# Sheet1.net
KiCad netlist of a schematic drawn in Altium Designer
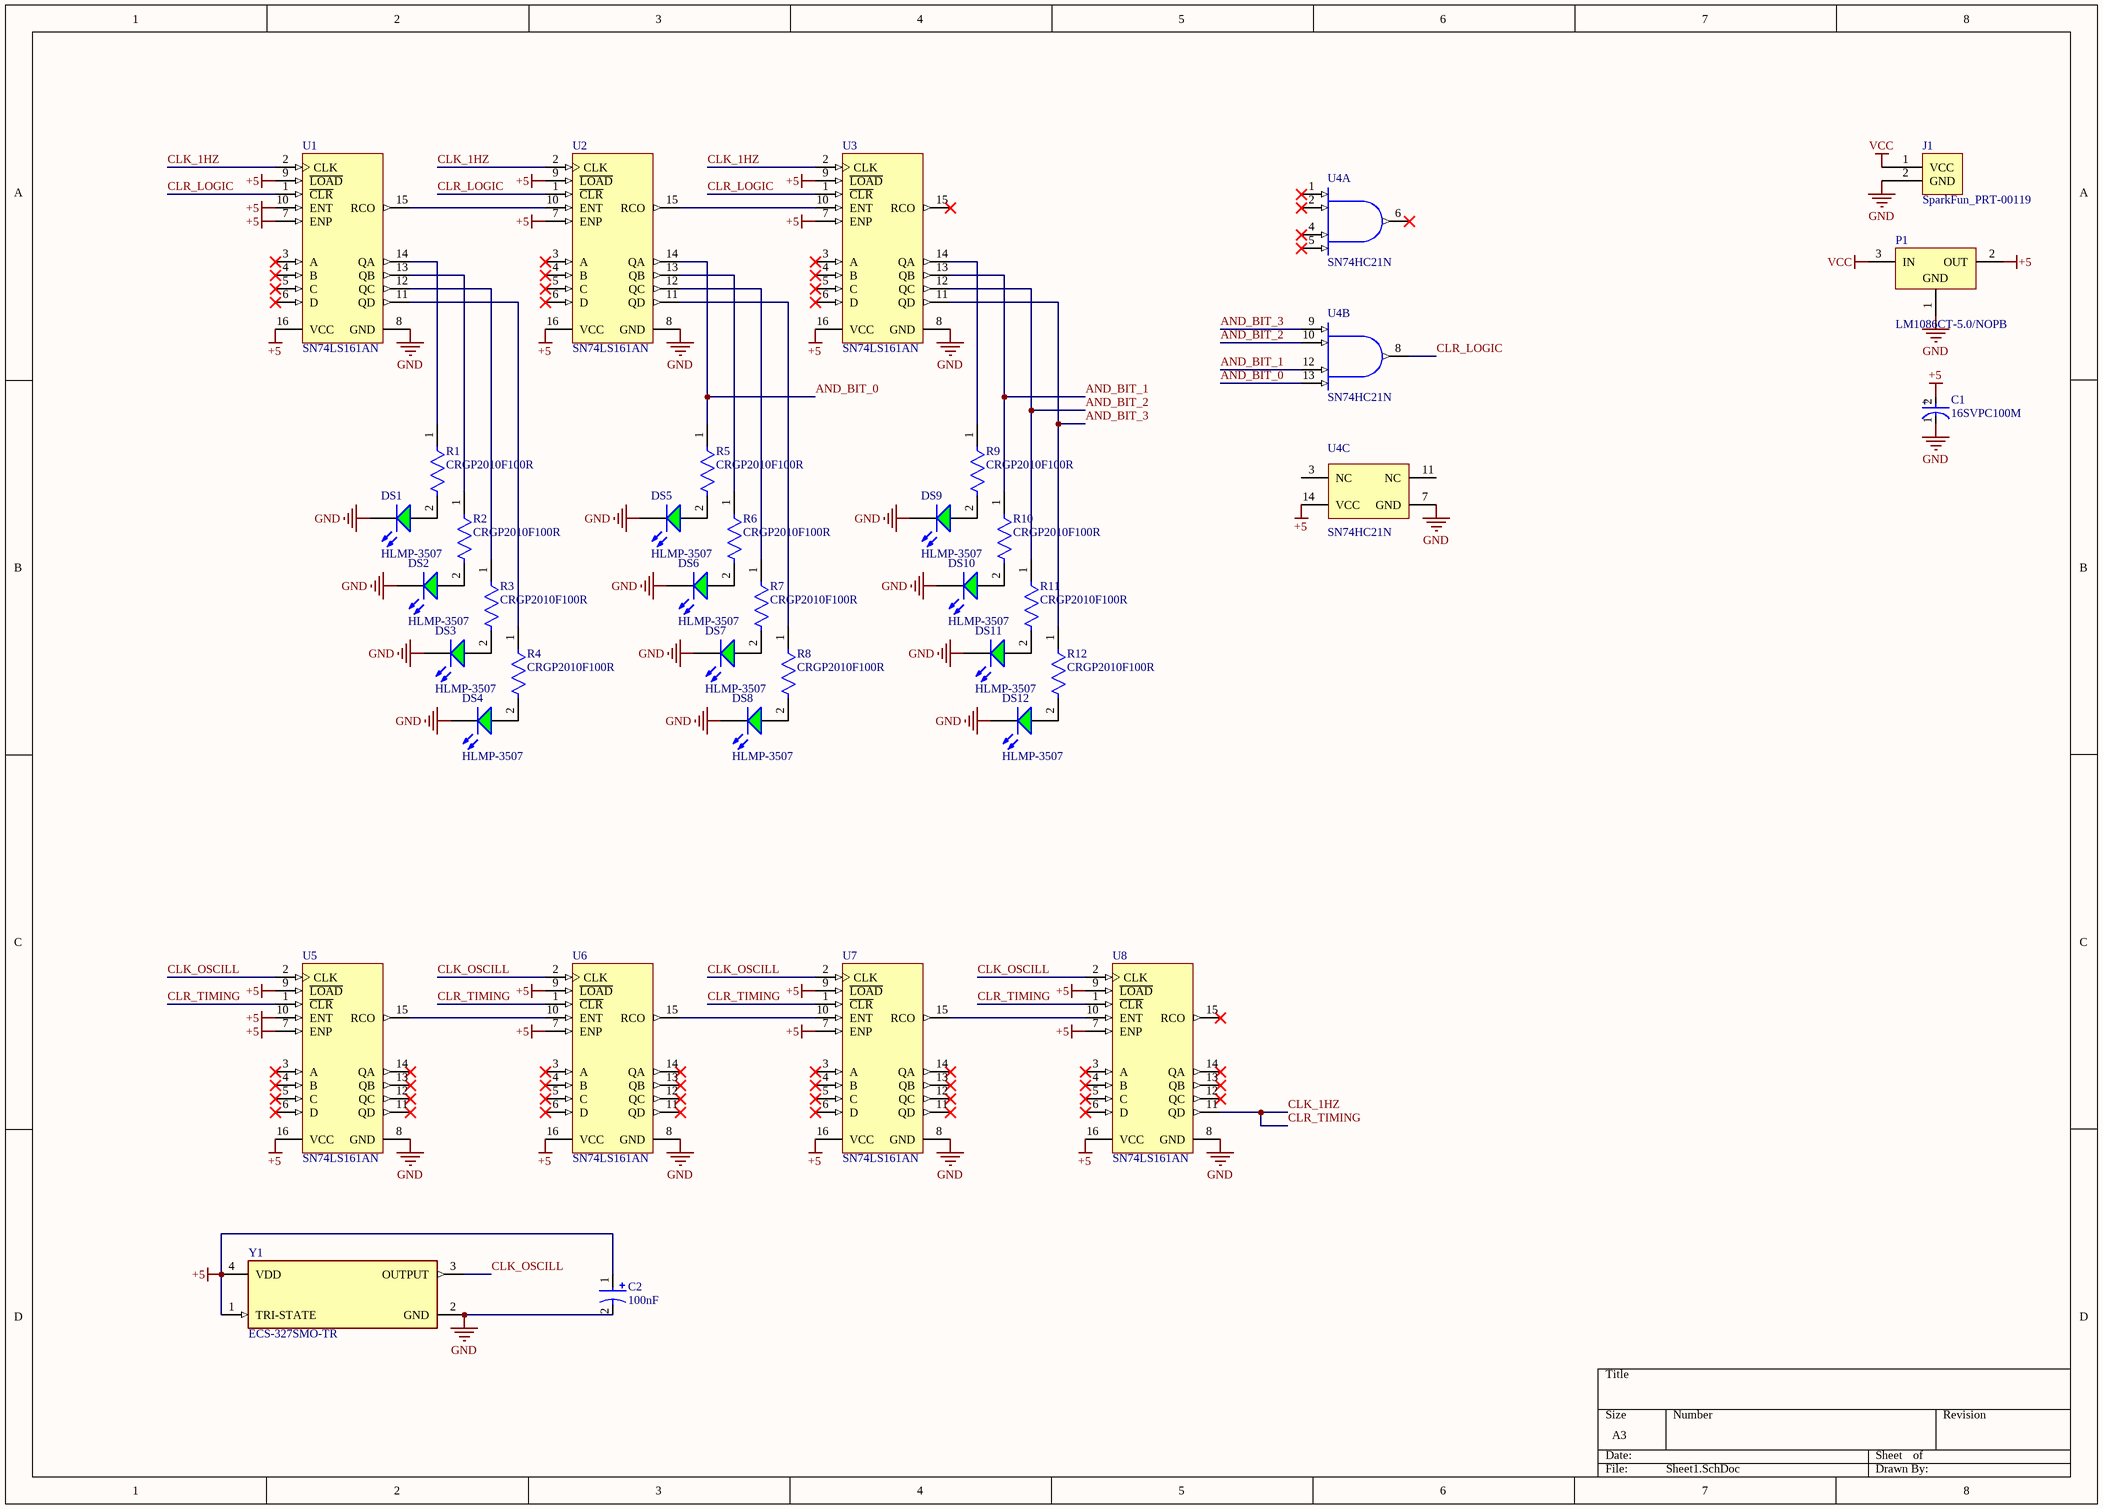
[diagram p0: Sheet1.SchDoc]

(export (version "E")
  (design (tool "Eeschema 10.0.6"))
  (components
    (comp (ref "C1")
      (value "16SVPC100M")
      (footprint "FP-OS-CON-SMT-C6-MFG")
      (description "Conductive Polymer Aluminum Solid Capacitors (OS-CON) 100uF ±20% 16V")
      (fields (field (name "VOLTAGE") "16V") (field (name "TOLERANCE") "20%"))
      (libsource (lib "Altium Content Vault") (part "a00bbbee19879c290e62620ae7e47b1"))
    )
    (comp (ref "C2")
      (value "100nF")
      (footprint "WurthElektronik_885012208030-Footprint-1")
      (description "Cap, 0.1ΜF, 16V, 10%, X7R, 1206")
      (fields (field (name "Comment") "WurthElektronik_885012208030"))
      (libsource (lib "Manus VR") (part "Capacitor_Polarized"))
    )
    (comp (ref "DS1")
      (value "HLMP-3507")
      (footprint "AVAG-HLMP-3507")
      (description "T-1 3/4 (5 mm) Diffused LED Lamp, Green, 2.1 V, -20 to 100 degC, 2-Pin THD, RoHS, Bulk")
      (fields (field (name "MANUFACTURER") "Avago"))
      (libsource (lib "Altium Content Vault") (part "LED-GREEN-AK-2"))
    )
    (comp (ref "DS2")
      (value "HLMP-3507")
      (footprint "AVAG-HLMP-3507")
      (description "T-1 3/4 (5 mm) Diffused LED Lamp, Green, 2.1 V, -20 to 100 degC, 2-Pin THD, RoHS, Bulk")
      (fields (field (name "MANUFACTURER") "Avago"))
      (libsource (lib "Altium Content Vault") (part "LED-GREEN-AK-2"))
    )
    (comp (ref "DS3")
      (value "HLMP-3507")
      (footprint "AVAG-HLMP-3507")
      (description "T-1 3/4 (5 mm) Diffused LED Lamp, Green, 2.1 V, -20 to 100 degC, 2-Pin THD, RoHS, Bulk")
      (fields (field (name "MANUFACTURER") "Avago"))
      (libsource (lib "Altium Content Vault") (part "LED-GREEN-AK-2"))
    )
    (comp (ref "DS4")
      (value "HLMP-3507")
      (footprint "AVAG-HLMP-3507")
      (description "T-1 3/4 (5 mm) Diffused LED Lamp, Green, 2.1 V, -20 to 100 degC, 2-Pin THD, RoHS, Bulk")
      (fields (field (name "MANUFACTURER") "Avago"))
      (libsource (lib "Altium Content Vault") (part "LED-GREEN-AK-2"))
    )
    (comp (ref "DS5")
      (value "HLMP-3507")
      (footprint "AVAG-HLMP-3507")
      (description "T-1 3/4 (5 mm) Diffused LED Lamp, Green, 2.1 V, -20 to 100 degC, 2-Pin THD, RoHS, Bulk")
      (fields (field (name "MANUFACTURER") "Avago"))
      (libsource (lib "Altium Content Vault") (part "LED-GREEN-AK-2"))
    )
    (comp (ref "DS6")
      (value "HLMP-3507")
      (footprint "AVAG-HLMP-3507")
      (description "T-1 3/4 (5 mm) Diffused LED Lamp, Green, 2.1 V, -20 to 100 degC, 2-Pin THD, RoHS, Bulk")
      (fields (field (name "MANUFACTURER") "Avago"))
      (libsource (lib "Altium Content Vault") (part "LED-GREEN-AK-2"))
    )
    (comp (ref "DS7")
      (value "HLMP-3507")
      (footprint "AVAG-HLMP-3507")
      (description "T-1 3/4 (5 mm) Diffused LED Lamp, Green, 2.1 V, -20 to 100 degC, 2-Pin THD, RoHS, Bulk")
      (fields (field (name "MANUFACTURER") "Avago"))
      (libsource (lib "Altium Content Vault") (part "LED-GREEN-AK-2"))
    )
    (comp (ref "DS8")
      (value "HLMP-3507")
      (footprint "AVAG-HLMP-3507")
      (description "T-1 3/4 (5 mm) Diffused LED Lamp, Green, 2.1 V, -20 to 100 degC, 2-Pin THD, RoHS, Bulk")
      (fields (field (name "MANUFACTURER") "Avago"))
      (libsource (lib "Altium Content Vault") (part "LED-GREEN-AK-2"))
    )
    (comp (ref "DS9")
      (value "HLMP-3507")
      (footprint "AVAG-HLMP-3507")
      (description "T-1 3/4 (5 mm) Diffused LED Lamp, Green, 2.1 V, -20 to 100 degC, 2-Pin THD, RoHS, Bulk")
      (fields (field (name "MANUFACTURER") "Avago"))
      (libsource (lib "Altium Content Vault") (part "LED-GREEN-AK-2"))
    )
    (comp (ref "DS10")
      (value "HLMP-3507")
      (footprint "AVAG-HLMP-3507")
      (description "T-1 3/4 (5 mm) Diffused LED Lamp, Green, 2.1 V, -20 to 100 degC, 2-Pin THD, RoHS, Bulk")
      (fields (field (name "MANUFACTURER") "Avago"))
      (libsource (lib "Altium Content Vault") (part "LED-GREEN-AK-2"))
    )
    (comp (ref "DS11")
      (value "HLMP-3507")
      (footprint "AVAG-HLMP-3507")
      (description "T-1 3/4 (5 mm) Diffused LED Lamp, Green, 2.1 V, -20 to 100 degC, 2-Pin THD, RoHS, Bulk")
      (fields (field (name "MANUFACTURER") "Avago"))
      (libsource (lib "Altium Content Vault") (part "LED-GREEN-AK-2"))
    )
    (comp (ref "DS12")
      (value "HLMP-3507")
      (footprint "AVAG-HLMP-3507")
      (description "T-1 3/4 (5 mm) Diffused LED Lamp, Green, 2.1 V, -20 to 100 degC, 2-Pin THD, RoHS, Bulk")
      (fields (field (name "MANUFACTURER") "Avago"))
      (libsource (lib "Altium Content Vault") (part "LED-GREEN-AK-2"))
    )
    (comp (ref "J1")
      (value "SparkFun_PRT-00119")
      (footprint "SparkFun_PRT-00119-Footprint-1")
      (description "Simple 6.5mm barrel jack connector")
      (fields (field (name "MANUFACTURER") "SparkFun") (field (name "MPN") "PRT-00119"))
      (libsource (lib "Manus VR") (part "SparkFun_PRT-00119-Symbol-1"))
    )
    (comp (ref "P1")
      (value "LM1086CT-5.0/NOPB")
      (footprint "NDE0003A")
      (description "1.5A Low Dropout Positive Regulators, 3-pin TO-220, Pb-Free")
      (fields (field (name "MANUFACTURER") "Texas Instruments"))
      (libsource (lib "Altium Content Vault") (part "PM-REG-LM1086-SIL3"))
    )
    (comp (ref "R1")
      (value "CRGP2010F100R")
      (footprint "FP-CRGP2010-IPC_C")
      (description "CRGP2010 100Ω 1.25W ±100ppm/°C 1% 400V")
      (fields
        (field (name "MANUFACTURER") "TE")
        (field (name "OCTOPART") "https://octopart.com/crgp2010f100r-te+connectivity-91018964")
      )
      (libsource (lib "Altium Content Vault") (part "1029c3af85768c4190bb7ad29bc67b5"))
    )
    (comp (ref "R2")
      (value "CRGP2010F100R")
      (footprint "FP-CRGP2010-IPC_C")
      (description "CRGP2010 100Ω 1.25W ±100ppm/°C 1% 400V")
      (fields
        (field (name "MANUFACTURER") "TE")
        (field (name "OCTOPART") "https://octopart.com/crgp2010f100r-te+connectivity-91018964")
      )
      (libsource (lib "Altium Content Vault") (part "1029c3af85768c4190bb7ad29bc67b5"))
    )
    (comp (ref "R3")
      (value "CRGP2010F100R")
      (footprint "FP-CRGP2010-IPC_C")
      (description "CRGP2010 100Ω 1.25W ±100ppm/°C 1% 400V")
      (fields
        (field (name "MANUFACTURER") "TE")
        (field (name "OCTOPART") "https://octopart.com/crgp2010f100r-te+connectivity-91018964")
      )
      (libsource (lib "Altium Content Vault") (part "1029c3af85768c4190bb7ad29bc67b5"))
    )
    (comp (ref "R4")
      (value "CRGP2010F100R")
      (footprint "FP-CRGP2010-IPC_C")
      (description "CRGP2010 100Ω 1.25W ±100ppm/°C 1% 400V")
      (fields
        (field (name "MANUFACTURER") "TE")
        (field (name "OCTOPART") "https://octopart.com/crgp2010f100r-te+connectivity-91018964")
      )
      (libsource (lib "Altium Content Vault") (part "1029c3af85768c4190bb7ad29bc67b5"))
    )
    (comp (ref "R5")
      (value "CRGP2010F100R")
      (footprint "FP-CRGP2010-IPC_C")
      (description "CRGP2010 100Ω 1.25W ±100ppm/°C 1% 400V")
      (fields
        (field (name "MANUFACTURER") "TE")
        (field (name "OCTOPART") "https://octopart.com/crgp2010f100r-te+connectivity-91018964")
      )
      (libsource (lib "Altium Content Vault") (part "1029c3af85768c4190bb7ad29bc67b5"))
    )
    (comp (ref "R6")
      (value "CRGP2010F100R")
      (footprint "FP-CRGP2010-IPC_C")
      (description "CRGP2010 100Ω 1.25W ±100ppm/°C 1% 400V")
      (fields
        (field (name "MANUFACTURER") "TE")
        (field (name "OCTOPART") "https://octopart.com/crgp2010f100r-te+connectivity-91018964")
      )
      (libsource (lib "Altium Content Vault") (part "1029c3af85768c4190bb7ad29bc67b5"))
    )
    (comp (ref "R7")
      (value "CRGP2010F100R")
      (footprint "FP-CRGP2010-IPC_C")
      (description "CRGP2010 100Ω 1.25W ±100ppm/°C 1% 400V")
      (fields
        (field (name "MANUFACTURER") "TE")
        (field (name "OCTOPART") "https://octopart.com/crgp2010f100r-te+connectivity-91018964")
      )
      (libsource (lib "Altium Content Vault") (part "1029c3af85768c4190bb7ad29bc67b5"))
    )
    (comp (ref "R8")
      (value "CRGP2010F100R")
      (footprint "FP-CRGP2010-IPC_C")
      (description "CRGP2010 100Ω 1.25W ±100ppm/°C 1% 400V")
      (fields
        (field (name "MANUFACTURER") "TE")
        (field (name "OCTOPART") "https://octopart.com/crgp2010f100r-te+connectivity-91018964")
      )
      (libsource (lib "Altium Content Vault") (part "1029c3af85768c4190bb7ad29bc67b5"))
    )
    (comp (ref "R9")
      (value "CRGP2010F100R")
      (footprint "FP-CRGP2010-IPC_C")
      (description "CRGP2010 100Ω 1.25W ±100ppm/°C 1% 400V")
      (fields
        (field (name "MANUFACTURER") "TE")
        (field (name "OCTOPART") "https://octopart.com/crgp2010f100r-te+connectivity-91018964")
      )
      (libsource (lib "Altium Content Vault") (part "1029c3af85768c4190bb7ad29bc67b5"))
    )
    (comp (ref "R10")
      (value "CRGP2010F100R")
      (footprint "FP-CRGP2010-IPC_C")
      (description "CRGP2010 100Ω 1.25W ±100ppm/°C 1% 400V")
      (fields
        (field (name "MANUFACTURER") "TE")
        (field (name "OCTOPART") "https://octopart.com/crgp2010f100r-te+connectivity-91018964")
      )
      (libsource (lib "Altium Content Vault") (part "1029c3af85768c4190bb7ad29bc67b5"))
    )
    (comp (ref "R11")
      (value "CRGP2010F100R")
      (footprint "FP-CRGP2010-IPC_C")
      (description "CRGP2010 100Ω 1.25W ±100ppm/°C 1% 400V")
      (fields
        (field (name "MANUFACTURER") "TE")
        (field (name "OCTOPART") "https://octopart.com/crgp2010f100r-te+connectivity-91018964")
      )
      (libsource (lib "Altium Content Vault") (part "1029c3af85768c4190bb7ad29bc67b5"))
    )
    (comp (ref "R12")
      (value "CRGP2010F100R")
      (footprint "FP-CRGP2010-IPC_C")
      (description "CRGP2010 100Ω 1.25W ±100ppm/°C 1% 400V")
      (fields
        (field (name "MANUFACTURER") "TE")
        (field (name "OCTOPART") "https://octopart.com/crgp2010f100r-te+connectivity-91018964")
      )
      (libsource (lib "Altium Content Vault") (part "1029c3af85768c4190bb7ad29bc67b5"))
    )
    (comp (ref "U1")
      (value "SN74LS161AN")
      (footprint "N0016A")
      (description "Synchronous 4-Bit Binary Counters, N0016A, TUBE")
      (fields
        (field (name "GENERIC PART NUMBER") "SN74LS161A")
        (field (name "MANUFACTURER") "Texas Instruments")
      )
      (libsource (lib "Altium Content Vault") (part "TI-CD_SNX4XXX161_163X-16"))
    )
    (comp (ref "U2")
      (value "SN74LS161AN")
      (footprint "N0016A")
      (description "Synchronous 4-Bit Binary Counters, N0016A, TUBE")
      (fields
        (field (name "GENERIC PART NUMBER") "SN74LS161A")
        (field (name "MANUFACTURER") "Texas Instruments")
      )
      (libsource (lib "Altium Content Vault") (part "TI-CD_SNX4XXX161_163X-16"))
    )
    (comp (ref "U3")
      (value "SN74LS161AN")
      (footprint "N0016A")
      (description "Synchronous 4-Bit Binary Counters, N0016A, TUBE")
      (fields
        (field (name "GENERIC PART NUMBER") "SN74LS161A")
        (field (name "MANUFACTURER") "Texas Instruments")
      )
      (libsource (lib "Altium Content Vault") (part "TI-CD_SNX4XXX161_163X-16"))
    )
    (comp (ref "U4")
      (value "SN74HC21N")
      (footprint "N0014A")
      (description "Dual 4-Input Positive-AND Gates, N0014A, TUBE")
      (fields
        (field (name "GENERIC PART NUMBER") "SN74HC21")
        (field (name "MANUFACTURER") "Texas Instruments")
      )
      (libsource (lib "Altium Content Vault") (part "TI-SNX4XXX21X-14"))
    )
    (comp (ref "U5")
      (value "SN74LS161AN")
      (footprint "N0016A")
      (description "Synchronous 4-Bit Binary Counters, N0016A, TUBE")
      (fields
        (field (name "GENERIC PART NUMBER") "SN74LS161A")
        (field (name "MANUFACTURER") "Texas Instruments")
      )
      (libsource (lib "Altium Content Vault") (part "TI-CD_SNX4XXX161_163X-16"))
    )
    (comp (ref "U6")
      (value "SN74LS161AN")
      (footprint "N0016A")
      (description "Synchronous 4-Bit Binary Counters, N0016A, TUBE")
      (fields
        (field (name "GENERIC PART NUMBER") "SN74LS161A")
        (field (name "MANUFACTURER") "Texas Instruments")
      )
      (libsource (lib "Altium Content Vault") (part "TI-CD_SNX4XXX161_163X-16"))
    )
    (comp (ref "U7")
      (value "SN74LS161AN")
      (footprint "N0016A")
      (description "Synchronous 4-Bit Binary Counters, N0016A, TUBE")
      (fields
        (field (name "GENERIC PART NUMBER") "SN74LS161A")
        (field (name "MANUFACTURER") "Texas Instruments")
      )
      (libsource (lib "Altium Content Vault") (part "TI-CD_SNX4XXX161_163X-16"))
    )
    (comp (ref "U8")
      (value "SN74LS161AN")
      (footprint "N0016A")
      (description "Synchronous 4-Bit Binary Counters, N0016A, TUBE")
      (fields
        (field (name "GENERIC PART NUMBER") "SN74LS161A")
        (field (name "MANUFACTURER") "Texas Instruments")
      )
      (libsource (lib "Altium Content Vault") (part "TI-CD_SNX4XXX161_163X-16"))
    )
    (comp (ref "Y1")
      (value "ECS-327SMO-TR")
      (footprint "FP-327SMO-MFG")
      (description "XTAL OSC XO 32.7680KHZ CMOS SMD")
      (libsource (lib "Altium Content Vault") (part "38dbe44cef64e428c8a2a88db308dd7"))
    )
  )
  (nets
    (net (code "1") (name "+5") (class "Default")
      (node (ref "C1") (pin "2") (pinfunction "A_2") (pintype "passive"))
      (node (ref "C2") (pin "1") (pinfunction "1_1") (pintype "passive"))
      (node (ref "P1") (pin "2") (pinfunction "OUT_2") (pintype "power_in"))
      (node (ref "U1") (pin "10") (pinfunction "ENT_10") (pintype "input"))
      (node (ref "U1") (pin "16") (pinfunction "VCC_16") (pintype "power_in"))
      (node (ref "U1") (pin "7") (pinfunction "ENP_7") (pintype "input"))
      (node (ref "U1") (pin "9") (pinfunction "~{LOAD}_9") (pintype "input"))
      (node (ref "U2") (pin "16") (pinfunction "VCC_16") (pintype "power_in"))
      (node (ref "U2") (pin "7") (pinfunction "ENP_7") (pintype "input"))
      (node (ref "U2") (pin "9") (pinfunction "~{LOAD}_9") (pintype "input"))
      (node (ref "U3") (pin "16") (pinfunction "VCC_16") (pintype "power_in"))
      (node (ref "U3") (pin "7") (pinfunction "ENP_7") (pintype "input"))
      (node (ref "U3") (pin "9") (pinfunction "~{LOAD}_9") (pintype "input"))
      (node (ref "U4") (pin "14") (pinfunction "VCC_14") (pintype "power_in"))
      (node (ref "U5") (pin "10") (pinfunction "ENT_10") (pintype "input"))
      (node (ref "U5") (pin "16") (pinfunction "VCC_16") (pintype "power_in"))
      (node (ref "U5") (pin "7") (pinfunction "ENP_7") (pintype "input"))
      (node (ref "U5") (pin "9") (pinfunction "~{LOAD}_9") (pintype "input"))
      (node (ref "U6") (pin "16") (pinfunction "VCC_16") (pintype "power_in"))
      (node (ref "U6") (pin "7") (pinfunction "ENP_7") (pintype "input"))
      (node (ref "U6") (pin "9") (pinfunction "~{LOAD}_9") (pintype "input"))
      (node (ref "U7") (pin "16") (pinfunction "VCC_16") (pintype "power_in"))
      (node (ref "U7") (pin "7") (pinfunction "ENP_7") (pintype "input"))
      (node (ref "U7") (pin "9") (pinfunction "~{LOAD}_9") (pintype "input"))
      (node (ref "U8") (pin "16") (pinfunction "VCC_16") (pintype "power_in"))
      (node (ref "U8") (pin "7") (pinfunction "ENP_7") (pintype "input"))
      (node (ref "U8") (pin "9") (pinfunction "~{LOAD}_9") (pintype "input"))
      (node (ref "Y1") (pin "1") (pinfunction "TRI-STATE_1") (pintype "input"))
      (node (ref "Y1") (pin "4") (pinfunction "VDD_4") (pintype "power_in"))
    )
    (net (code "2") (name "/AND_BIT_0") (class "Default")
      (node (ref "R5") (pin "1") (pinfunction "1_1") (pintype "passive"))
      (node (ref "U2") (pin "14") (pinfunction "QA_14") (pintype "output"))
      (node (ref "U4") (pin "13") (pinfunction "2D_13") (pintype "input"))
    )
    (net (code "3") (name "/AND_BIT_1") (class "Default")
      (node (ref "R10") (pin "1") (pinfunction "1_1") (pintype "passive"))
      (node (ref "U3") (pin "13") (pinfunction "QB_13") (pintype "output"))
      (node (ref "U4") (pin "12") (pinfunction "2C_12") (pintype "input"))
    )
    (net (code "4") (name "/AND_BIT_2") (class "Default")
      (node (ref "R11") (pin "1") (pinfunction "1_1") (pintype "passive"))
      (node (ref "U3") (pin "12") (pinfunction "QC_12") (pintype "output"))
      (node (ref "U4") (pin "10") (pinfunction "2B_10") (pintype "input"))
    )
    (net (code "5") (name "/AND_BIT_3") (class "Default")
      (node (ref "R12") (pin "1") (pinfunction "1_1") (pintype "passive"))
      (node (ref "U3") (pin "11") (pinfunction "QD_11") (pintype "output"))
      (node (ref "U4") (pin "9") (pinfunction "2A_9") (pintype "input"))
    )
    (net (code "6") (name "/CLK_1HZ") (class "Default")
      (node (ref "U1") (pin "2") (pinfunction "CLK_2") (pintype "input"))
      (node (ref "U2") (pin "2") (pinfunction "CLK_2") (pintype "input"))
      (node (ref "U3") (pin "2") (pinfunction "CLK_2") (pintype "input"))
      (node (ref "U5") (pin "1") (pinfunction "~{CLR}_1") (pintype "input"))
      (node (ref "U6") (pin "1") (pinfunction "~{CLR}_1") (pintype "input"))
      (node (ref "U7") (pin "1") (pinfunction "~{CLR}_1") (pintype "input"))
      (node (ref "U8") (pin "1") (pinfunction "~{CLR}_1") (pintype "input"))
      (node (ref "U8") (pin "11") (pinfunction "QD_11") (pintype "output"))
    )
    (net (code "7") (name "/CLK_OSCILL") (class "Default")
      (node (ref "U5") (pin "2") (pinfunction "CLK_2") (pintype "input"))
      (node (ref "U6") (pin "2") (pinfunction "CLK_2") (pintype "input"))
      (node (ref "U7") (pin "2") (pinfunction "CLK_2") (pintype "input"))
      (node (ref "U8") (pin "2") (pinfunction "CLK_2") (pintype "input"))
      (node (ref "Y1") (pin "3") (pinfunction "OUTPUT_3") (pintype "output"))
    )
    (net (code "8") (name "/CLR_LOGIC") (class "Default")
      (node (ref "U1") (pin "1") (pinfunction "~{CLR}_1") (pintype "input"))
      (node (ref "U2") (pin "1") (pinfunction "~{CLR}_1") (pintype "input"))
      (node (ref "U3") (pin "1") (pinfunction "~{CLR}_1") (pintype "input"))
      (node (ref "U4") (pin "8") (pinfunction "2Y_8") (pintype "output"))
    )
    (net (code "9") (name "GND") (class "Default")
      (node (ref "C1") (pin "1") (pinfunction "C_1") (pintype "passive"))
      (node (ref "C2") (pin "2") (pinfunction "2_2") (pintype "passive"))
      (node (ref "DS1") (pin "2") (pinfunction "K_2") (pintype "passive"))
      (node (ref "DS10") (pin "2") (pinfunction "K_2") (pintype "passive"))
      (node (ref "DS11") (pin "2") (pinfunction "K_2") (pintype "passive"))
      (node (ref "DS12") (pin "2") (pinfunction "K_2") (pintype "passive"))
      (node (ref "DS2") (pin "2") (pinfunction "K_2") (pintype "passive"))
      (node (ref "DS3") (pin "2") (pinfunction "K_2") (pintype "passive"))
      (node (ref "DS4") (pin "2") (pinfunction "K_2") (pintype "passive"))
      (node (ref "DS5") (pin "2") (pinfunction "K_2") (pintype "passive"))
      (node (ref "DS6") (pin "2") (pinfunction "K_2") (pintype "passive"))
      (node (ref "DS7") (pin "2") (pinfunction "K_2") (pintype "passive"))
      (node (ref "DS8") (pin "2") (pinfunction "K_2") (pintype "passive"))
      (node (ref "DS9") (pin "2") (pinfunction "K_2") (pintype "passive"))
      (node (ref "J1") (pin "2") (pinfunction "GND_2") (pintype "power_in"))
      (node (ref "P1") (pin "1") (pinfunction "GND_1") (pintype "power_in"))
      (node (ref "U1") (pin "8") (pinfunction "GND_8") (pintype "power_in"))
      (node (ref "U2") (pin "8") (pinfunction "GND_8") (pintype "power_in"))
      (node (ref "U3") (pin "8") (pinfunction "GND_8") (pintype "power_in"))
      (node (ref "U4") (pin "7") (pinfunction "GND_7") (pintype "power_in"))
      (node (ref "U5") (pin "8") (pinfunction "GND_8") (pintype "power_in"))
      (node (ref "U6") (pin "8") (pinfunction "GND_8") (pintype "power_in"))
      (node (ref "U7") (pin "8") (pinfunction "GND_8") (pintype "power_in"))
      (node (ref "U8") (pin "8") (pinfunction "GND_8") (pintype "power_in"))
      (node (ref "Y1") (pin "2") (pinfunction "GND_2") (pintype "power_in"))
    )
    (net (code "10") (name "Net-(DS1-A)") (class "Default")
      (node (ref "DS1") (pin "1") (pinfunction "A_1") (pintype "passive"))
      (node (ref "R1") (pin "2") (pinfunction "2_2") (pintype "passive"))
    )
    (net (code "11") (name "Net-(DS2-A)") (class "Default")
      (node (ref "DS2") (pin "1") (pinfunction "A_1") (pintype "passive"))
      (node (ref "R2") (pin "2") (pinfunction "2_2") (pintype "passive"))
    )
    (net (code "12") (name "Net-(DS3-A)") (class "Default")
      (node (ref "DS3") (pin "1") (pinfunction "A_1") (pintype "passive"))
      (node (ref "R3") (pin "2") (pinfunction "2_2") (pintype "passive"))
    )
    (net (code "13") (name "Net-(DS4-A)") (class "Default")
      (node (ref "DS4") (pin "1") (pinfunction "A_1") (pintype "passive"))
      (node (ref "R4") (pin "2") (pinfunction "2_2") (pintype "passive"))
    )
    (net (code "14") (name "Net-(DS5-A)") (class "Default")
      (node (ref "DS5") (pin "1") (pinfunction "A_1") (pintype "passive"))
      (node (ref "R5") (pin "2") (pinfunction "2_2") (pintype "passive"))
    )
    (net (code "15") (name "Net-(DS6-A)") (class "Default")
      (node (ref "DS6") (pin "1") (pinfunction "A_1") (pintype "passive"))
      (node (ref "R6") (pin "2") (pinfunction "2_2") (pintype "passive"))
    )
    (net (code "16") (name "Net-(DS7-A)") (class "Default")
      (node (ref "DS7") (pin "1") (pinfunction "A_1") (pintype "passive"))
      (node (ref "R7") (pin "2") (pinfunction "2_2") (pintype "passive"))
    )
    (net (code "17") (name "Net-(DS8-A)") (class "Default")
      (node (ref "DS8") (pin "1") (pinfunction "A_1") (pintype "passive"))
      (node (ref "R8") (pin "2") (pinfunction "2_2") (pintype "passive"))
    )
    (net (code "18") (name "Net-(DS9-A)") (class "Default")
      (node (ref "DS9") (pin "1") (pinfunction "A_1") (pintype "passive"))
      (node (ref "R9") (pin "2") (pinfunction "2_2") (pintype "passive"))
    )
    (net (code "19") (name "Net-(DS10-A)") (class "Default")
      (node (ref "DS10") (pin "1") (pinfunction "A_1") (pintype "passive"))
      (node (ref "R10") (pin "2") (pinfunction "2_2") (pintype "passive"))
    )
    (net (code "20") (name "Net-(DS11-A)") (class "Default")
      (node (ref "DS11") (pin "1") (pinfunction "A_1") (pintype "passive"))
      (node (ref "R11") (pin "2") (pinfunction "2_2") (pintype "passive"))
    )
    (net (code "21") (name "Net-(DS12-A)") (class "Default")
      (node (ref "DS12") (pin "1") (pinfunction "A_1") (pintype "passive"))
      (node (ref "R12") (pin "2") (pinfunction "2_2") (pintype "passive"))
    )
    (net (code "22") (name "Net-(U1-QA)") (class "Default")
      (node (ref "R1") (pin "1") (pinfunction "1_1") (pintype "passive"))
      (node (ref "U1") (pin "14") (pinfunction "QA_14") (pintype "output"))
    )
    (net (code "23") (name "Net-(U1-QB)") (class "Default")
      (node (ref "R2") (pin "1") (pinfunction "1_1") (pintype "passive"))
      (node (ref "U1") (pin "13") (pinfunction "QB_13") (pintype "output"))
    )
    (net (code "24") (name "Net-(U1-QC)") (class "Default")
      (node (ref "R3") (pin "1") (pinfunction "1_1") (pintype "passive"))
      (node (ref "U1") (pin "12") (pinfunction "QC_12") (pintype "output"))
    )
    (net (code "25") (name "Net-(U1-QD)") (class "Default")
      (node (ref "R4") (pin "1") (pinfunction "1_1") (pintype "passive"))
      (node (ref "U1") (pin "11") (pinfunction "QD_11") (pintype "output"))
    )
    (net (code "26") (name "Net-(U1-RCO)") (class "Default")
      (node (ref "U1") (pin "15") (pinfunction "RCO_15") (pintype "output"))
      (node (ref "U2") (pin "10") (pinfunction "ENT_10") (pintype "input"))
    )
    (net (code "27") (name "Net-(U2-QB)") (class "Default")
      (node (ref "R6") (pin "1") (pinfunction "1_1") (pintype "passive"))
      (node (ref "U2") (pin "13") (pinfunction "QB_13") (pintype "output"))
    )
    (net (code "28") (name "Net-(U2-QC)") (class "Default")
      (node (ref "R7") (pin "1") (pinfunction "1_1") (pintype "passive"))
      (node (ref "U2") (pin "12") (pinfunction "QC_12") (pintype "output"))
    )
    (net (code "29") (name "Net-(U2-QD)") (class "Default")
      (node (ref "R8") (pin "1") (pinfunction "1_1") (pintype "passive"))
      (node (ref "U2") (pin "11") (pinfunction "QD_11") (pintype "output"))
    )
    (net (code "30") (name "Net-(U2-RCO)") (class "Default")
      (node (ref "U2") (pin "15") (pinfunction "RCO_15") (pintype "output"))
      (node (ref "U3") (pin "10") (pinfunction "ENT_10") (pintype "input"))
    )
    (net (code "31") (name "Net-(U3-QA)") (class "Default")
      (node (ref "R9") (pin "1") (pinfunction "1_1") (pintype "passive"))
      (node (ref "U3") (pin "14") (pinfunction "QA_14") (pintype "output"))
    )
    (net (code "32") (name "Net-(U5-RCO)") (class "Default")
      (node (ref "U5") (pin "15") (pinfunction "RCO_15") (pintype "output"))
      (node (ref "U6") (pin "10") (pinfunction "ENT_10") (pintype "input"))
    )
    (net (code "33") (name "Net-(U6-RCO)") (class "Default")
      (node (ref "U6") (pin "15") (pinfunction "RCO_15") (pintype "output"))
      (node (ref "U7") (pin "10") (pinfunction "ENT_10") (pintype "input"))
    )
    (net (code "34") (name "Net-(U7-RCO)") (class "Default")
      (node (ref "U7") (pin "15") (pinfunction "RCO_15") (pintype "output"))
      (node (ref "U8") (pin "10") (pinfunction "ENT_10") (pintype "input"))
    )
    (net (code "35") (name "VCC") (class "Default")
      (node (ref "J1") (pin "1") (pinfunction "VCC_1") (pintype "power_in"))
      (node (ref "P1") (pin "3") (pinfunction "IN_3") (pintype "power_in"))
    )
    (net (code "36") (name "unconnected-(U1-A-Pad3)") (class "Default")
      (node (ref "U1") (pin "3") (pinfunction "A_3") (pintype "input+no_connect"))
    )
    (net (code "37") (name "unconnected-(U1-B-Pad4)") (class "Default")
      (node (ref "U1") (pin "4") (pinfunction "B_4") (pintype "input+no_connect"))
    )
    (net (code "38") (name "unconnected-(U1-C-Pad5)") (class "Default")
      (node (ref "U1") (pin "5") (pinfunction "C_5") (pintype "input+no_connect"))
    )
    (net (code "39") (name "unconnected-(U1-D-Pad6)") (class "Default")
      (node (ref "U1") (pin "6") (pinfunction "D_6") (pintype "input+no_connect"))
    )
    (net (code "40") (name "unconnected-(U2-A-Pad3)") (class "Default")
      (node (ref "U2") (pin "3") (pinfunction "A_3") (pintype "input+no_connect"))
    )
    (net (code "41") (name "unconnected-(U2-B-Pad4)") (class "Default")
      (node (ref "U2") (pin "4") (pinfunction "B_4") (pintype "input+no_connect"))
    )
    (net (code "42") (name "unconnected-(U2-C-Pad5)") (class "Default")
      (node (ref "U2") (pin "5") (pinfunction "C_5") (pintype "input+no_connect"))
    )
    (net (code "43") (name "unconnected-(U2-D-Pad6)") (class "Default")
      (node (ref "U2") (pin "6") (pinfunction "D_6") (pintype "input+no_connect"))
    )
    (net (code "44") (name "unconnected-(U3-A-Pad3)") (class "Default")
      (node (ref "U3") (pin "3") (pinfunction "A_3") (pintype "input+no_connect"))
    )
    (net (code "45") (name "unconnected-(U3-B-Pad4)") (class "Default")
      (node (ref "U3") (pin "4") (pinfunction "B_4") (pintype "input+no_connect"))
    )
    (net (code "46") (name "unconnected-(U3-C-Pad5)") (class "Default")
      (node (ref "U3") (pin "5") (pinfunction "C_5") (pintype "input+no_connect"))
    )
    (net (code "47") (name "unconnected-(U3-D-Pad6)") (class "Default")
      (node (ref "U3") (pin "6") (pinfunction "D_6") (pintype "input+no_connect"))
    )
    (net (code "48") (name "unconnected-(U3-RCO-Pad15)") (class "Default")
      (node (ref "U3") (pin "15") (pinfunction "RCO_15") (pintype "output+no_connect"))
    )
    (net (code "49") (name "unconnected-(U4A-1A-Pad1)") (class "Default")
      (node (ref "U4") (pin "1") (pinfunction "1A_1") (pintype "input+no_connect"))
    )
    (net (code "50") (name "unconnected-(U4A-1B-Pad2)") (class "Default")
      (node (ref "U4") (pin "2") (pinfunction "1B_2") (pintype "input+no_connect"))
    )
    (net (code "51") (name "unconnected-(U4A-1C-Pad4)") (class "Default")
      (node (ref "U4") (pin "4") (pinfunction "1C_4") (pintype "input+no_connect"))
    )
    (net (code "52") (name "unconnected-(U4A-1D-Pad5)") (class "Default")
      (node (ref "U4") (pin "5") (pinfunction "1D_5") (pintype "input+no_connect"))
    )
    (net (code "53") (name "unconnected-(U4A-1Y-Pad6)") (class "Default")
      (node (ref "U4") (pin "6") (pinfunction "1Y_6") (pintype "output+no_connect"))
    )
    (net (code "54") (name "unconnected-(U4C-NC-Pad3)") (class "Default")
      (node (ref "U4") (pin "3") (pinfunction "NC_3") (pintype "passive"))
    )
    (net (code "55") (name "unconnected-(U4C-NC-Pad11)") (class "Default")
      (node (ref "U4") (pin "11") (pinfunction "NC_11") (pintype "passive"))
    )
    (net (code "56") (name "unconnected-(U5-A-Pad3)") (class "Default")
      (node (ref "U5") (pin "3") (pinfunction "A_3") (pintype "input+no_connect"))
    )
    (net (code "57") (name "unconnected-(U5-B-Pad4)") (class "Default")
      (node (ref "U5") (pin "4") (pinfunction "B_4") (pintype "input+no_connect"))
    )
    (net (code "58") (name "unconnected-(U5-C-Pad5)") (class "Default")
      (node (ref "U5") (pin "5") (pinfunction "C_5") (pintype "input+no_connect"))
    )
    (net (code "59") (name "unconnected-(U5-D-Pad6)") (class "Default")
      (node (ref "U5") (pin "6") (pinfunction "D_6") (pintype "input+no_connect"))
    )
    (net (code "60") (name "unconnected-(U5-QA-Pad14)") (class "Default")
      (node (ref "U5") (pin "14") (pinfunction "QA_14") (pintype "output+no_connect"))
    )
    (net (code "61") (name "unconnected-(U5-QB-Pad13)") (class "Default")
      (node (ref "U5") (pin "13") (pinfunction "QB_13") (pintype "output+no_connect"))
    )
    (net (code "62") (name "unconnected-(U5-QC-Pad12)") (class "Default")
      (node (ref "U5") (pin "12") (pinfunction "QC_12") (pintype "output+no_connect"))
    )
    (net (code "63") (name "unconnected-(U5-QD-Pad11)") (class "Default")
      (node (ref "U5") (pin "11") (pinfunction "QD_11") (pintype "output+no_connect"))
    )
    (net (code "64") (name "unconnected-(U6-A-Pad3)") (class "Default")
      (node (ref "U6") (pin "3") (pinfunction "A_3") (pintype "input+no_connect"))
    )
    (net (code "65") (name "unconnected-(U6-B-Pad4)") (class "Default")
      (node (ref "U6") (pin "4") (pinfunction "B_4") (pintype "input+no_connect"))
    )
    (net (code "66") (name "unconnected-(U6-C-Pad5)") (class "Default")
      (node (ref "U6") (pin "5") (pinfunction "C_5") (pintype "input+no_connect"))
    )
    (net (code "67") (name "unconnected-(U6-D-Pad6)") (class "Default")
      (node (ref "U6") (pin "6") (pinfunction "D_6") (pintype "input+no_connect"))
    )
    (net (code "68") (name "unconnected-(U6-QA-Pad14)") (class "Default")
      (node (ref "U6") (pin "14") (pinfunction "QA_14") (pintype "output+no_connect"))
    )
    (net (code "69") (name "unconnected-(U6-QB-Pad13)") (class "Default")
      (node (ref "U6") (pin "13") (pinfunction "QB_13") (pintype "output+no_connect"))
    )
    (net (code "70") (name "unconnected-(U6-QC-Pad12)") (class "Default")
      (node (ref "U6") (pin "12") (pinfunction "QC_12") (pintype "output+no_connect"))
    )
    (net (code "71") (name "unconnected-(U6-QD-Pad11)") (class "Default")
      (node (ref "U6") (pin "11") (pinfunction "QD_11") (pintype "output+no_connect"))
    )
    (net (code "72") (name "unconnected-(U7-A-Pad3)") (class "Default")
      (node (ref "U7") (pin "3") (pinfunction "A_3") (pintype "input+no_connect"))
    )
    (net (code "73") (name "unconnected-(U7-B-Pad4)") (class "Default")
      (node (ref "U7") (pin "4") (pinfunction "B_4") (pintype "input+no_connect"))
    )
    (net (code "74") (name "unconnected-(U7-C-Pad5)") (class "Default")
      (node (ref "U7") (pin "5") (pinfunction "C_5") (pintype "input+no_connect"))
    )
    (net (code "75") (name "unconnected-(U7-D-Pad6)") (class "Default")
      (node (ref "U7") (pin "6") (pinfunction "D_6") (pintype "input+no_connect"))
    )
    (net (code "76") (name "unconnected-(U7-QA-Pad14)") (class "Default")
      (node (ref "U7") (pin "14") (pinfunction "QA_14") (pintype "output+no_connect"))
    )
    (net (code "77") (name "unconnected-(U7-QB-Pad13)") (class "Default")
      (node (ref "U7") (pin "13") (pinfunction "QB_13") (pintype "output+no_connect"))
    )
    (net (code "78") (name "unconnected-(U7-QC-Pad12)") (class "Default")
      (node (ref "U7") (pin "12") (pinfunction "QC_12") (pintype "output+no_connect"))
    )
    (net (code "79") (name "unconnected-(U7-QD-Pad11)") (class "Default")
      (node (ref "U7") (pin "11") (pinfunction "QD_11") (pintype "output+no_connect"))
    )
    (net (code "80") (name "unconnected-(U8-A-Pad3)") (class "Default")
      (node (ref "U8") (pin "3") (pinfunction "A_3") (pintype "input+no_connect"))
    )
    (net (code "81") (name "unconnected-(U8-B-Pad4)") (class "Default")
      (node (ref "U8") (pin "4") (pinfunction "B_4") (pintype "input+no_connect"))
    )
    (net (code "82") (name "unconnected-(U8-C-Pad5)") (class "Default")
      (node (ref "U8") (pin "5") (pinfunction "C_5") (pintype "input+no_connect"))
    )
    (net (code "83") (name "unconnected-(U8-D-Pad6)") (class "Default")
      (node (ref "U8") (pin "6") (pinfunction "D_6") (pintype "input+no_connect"))
    )
    (net (code "84") (name "unconnected-(U8-QA-Pad14)") (class "Default")
      (node (ref "U8") (pin "14") (pinfunction "QA_14") (pintype "output+no_connect"))
    )
    (net (code "85") (name "unconnected-(U8-QB-Pad13)") (class "Default")
      (node (ref "U8") (pin "13") (pinfunction "QB_13") (pintype "output+no_connect"))
    )
    (net (code "86") (name "unconnected-(U8-QC-Pad12)") (class "Default")
      (node (ref "U8") (pin "12") (pinfunction "QC_12") (pintype "output+no_connect"))
    )
    (net (code "87") (name "unconnected-(U8-RCO-Pad15)") (class "Default")
      (node (ref "U8") (pin "15") (pinfunction "RCO_15") (pintype "output+no_connect"))
    )
  )
)
